# Thruster_rev2_1.net
KiCad netlist of a schematic drawn in Altium Designer
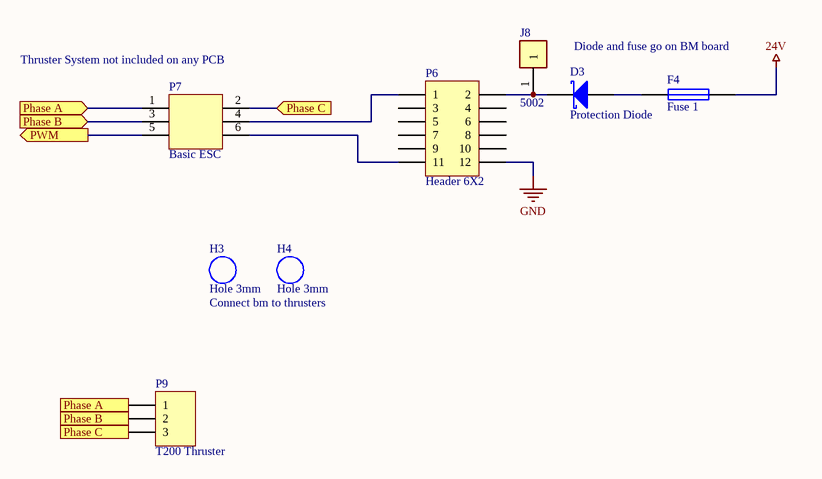
[diagram p0: Thruster_rev2 (1).SchDoc]

(export (version "E")
  (design (tool "Eeschema 10.0.6"))
  (components
    (comp (ref "D3")
      (value "Protection Diode")
      (footprint "TO-220AC")
      (description "Schottky Rectifier")
      (fields (field (name "PUBLISHER") "Altium Limited"))
      (libsource (lib "Miscellaneous Devices") (part "Diode 10TQ035"))
    )
    (comp (ref "F4")
      (value "Fuse 1")
      (footprint "PIN-W2/E2.8")
      (description "Fuse")
      (fields (field (name "PUBLISHER") "Altium Limited"))
      (libsource (lib "Miscellaneous Devices") (part "Fuse 1"))
    )
    (comp (ref "H3")
      (value "Hole 3mm")
      (footprint "Hole 3mm")
      (libsource (lib "ECE LIB 21") (part "Hole 3mm"))
    )
    (comp (ref "H4")
      (value "Hole 3mm")
      (footprint "Hole 3mm")
      (libsource (lib "ECE LIB 21") (part "Hole 3mm"))
    )
    (comp (ref "J8")
      (value "5002")
      (footprint "KEYSTONE_5002")
      (description "2.2ÂµH Shielded Wirewound Inductor 1.8A 66mOhm Max Nonstandard")
      (fields (field (name "MF") "Keystone Electronics"))
      (libsource (lib "5002") (part "5002"))
    )
    (comp (ref "P6")
      (value "Header 6X2")
      (footprint "HDR2X6")
      (description "2x6 position wire screw connector block")
      (fields (field (name "PUBLISHER") "Altium Limited"))
      (libsource (lib "Miscellaneous Connectors") (part "Header 6X2"))
    )
    (comp (ref "P7")
      (value "Basic ESC")
      (footprint "HDR2X3")
      (fields (field (name "PUBLISHER") "Altium Limited"))
      (libsource (lib "Miscellaneous Connectors") (part "Header 3X2"))
    )
    (comp (ref "P9")
      (value "T200 Thruster")
      (footprint "HDR1X3")
      (description "Header, 3-Pin")
      (fields (field (name "PUBLISHER") "Altium Limited"))
      (libsource (lib "Miscellaneous Connectors") (part "Header 3"))
    )
  )
  (nets
    (net (code "1") (name "/PWM") (class "Default")
      (node (ref "P7") (pin "5") (pinfunction "PWM_5") (pintype "passive"))
    )
    (net (code "2") (name "/Phase A") (class "Default")
      (node (ref "P7") (pin "1") (pinfunction "Phase_A_1") (pintype "passive"))
      (node (ref "P9") (pin "1") (pinfunction "1_1") (pintype "passive"))
    )
    (net (code "3") (name "/Phase B") (class "Default")
      (node (ref "P7") (pin "3") (pinfunction "Phase_C_3") (pintype "passive"))
      (node (ref "P9") (pin "2") (pinfunction "2_2") (pintype "passive"))
    )
    (net (code "4") (name "/Phase C") (class "Default")
      (node (ref "P7") (pin "2") (pinfunction "Phase_B_2") (pintype "passive"))
      (node (ref "P9") (pin "3") (pinfunction "3_3") (pintype "passive"))
    )
    (net (code "5") (name "24V") (class "Default")
      (node (ref "F4") (pin "1") (pinfunction "1_1") (pintype "passive"))
    )
    (net (code "6") (name "GND") (class "Default")
      (node (ref "P6") (pin "12") (pinfunction "12_12") (pintype "passive"))
    )
    (net (code "7") (name "Net-(D3-A)") (class "Default")
      (node (ref "D3") (pin "3") (pinfunction "A_3") (pintype "passive"))
      (node (ref "F4") (pin "2") (pinfunction "2_2") (pintype "passive"))
    )
    (net (code "8") (name "Net-(D3-K)") (class "Default")
      (node (ref "D3") (pin "1") (pinfunction "K_1") (pintype "passive"))
      (node (ref "J8") (pin "1") (pinfunction "1_1") (pintype "passive"))
      (node (ref "P6") (pin "2") (pinfunction "2_2") (pintype "passive"))
    )
    (net (code "9") (name "Net-(P7-GND)") (class "Default")
      (node (ref "P6") (pin "11") (pinfunction "11_11") (pintype "passive"))
      (node (ref "P7") (pin "6") (pinfunction "GND_6") (pintype "passive"))
    )
    (net (code "10") (name "Net-(P7-V+)") (class "Default")
      (node (ref "P6") (pin "1") (pinfunction "1_1") (pintype "passive"))
      (node (ref "P7") (pin "4") (pinfunction "V+_4") (pintype "passive"))
    )
    (net (code "11") (name "unconnected-(P6-Pad3)") (class "Default")
      (node (ref "P6") (pin "3") (pinfunction "3_3") (pintype "passive"))
    )
    (net (code "12") (name "unconnected-(P6-Pad4)") (class "Default")
      (node (ref "P6") (pin "4") (pinfunction "4_4") (pintype "passive"))
    )
    (net (code "13") (name "unconnected-(P6-Pad5)") (class "Default")
      (node (ref "P6") (pin "5") (pinfunction "5_5") (pintype "passive"))
    )
    (net (code "14") (name "unconnected-(P6-Pad6)") (class "Default")
      (node (ref "P6") (pin "6") (pinfunction "6_6") (pintype "passive"))
    )
    (net (code "15") (name "unconnected-(P6-Pad7)") (class "Default")
      (node (ref "P6") (pin "7") (pinfunction "7_7") (pintype "passive"))
    )
    (net (code "16") (name "unconnected-(P6-Pad8)") (class "Default")
      (node (ref "P6") (pin "8") (pinfunction "8_8") (pintype "passive"))
    )
    (net (code "17") (name "unconnected-(P6-Pad9)") (class "Default")
      (node (ref "P6") (pin "9") (pinfunction "9_9") (pintype "passive"))
    )
    (net (code "18") (name "unconnected-(P6-Pad10)") (class "Default")
      (node (ref "P6") (pin "10") (pinfunction "10_10") (pintype "passive"))
    )
  )
)
